# ChipTestBoardQFN32-r2.net
KiCad netlist of a schematic drawn in Altium Designer
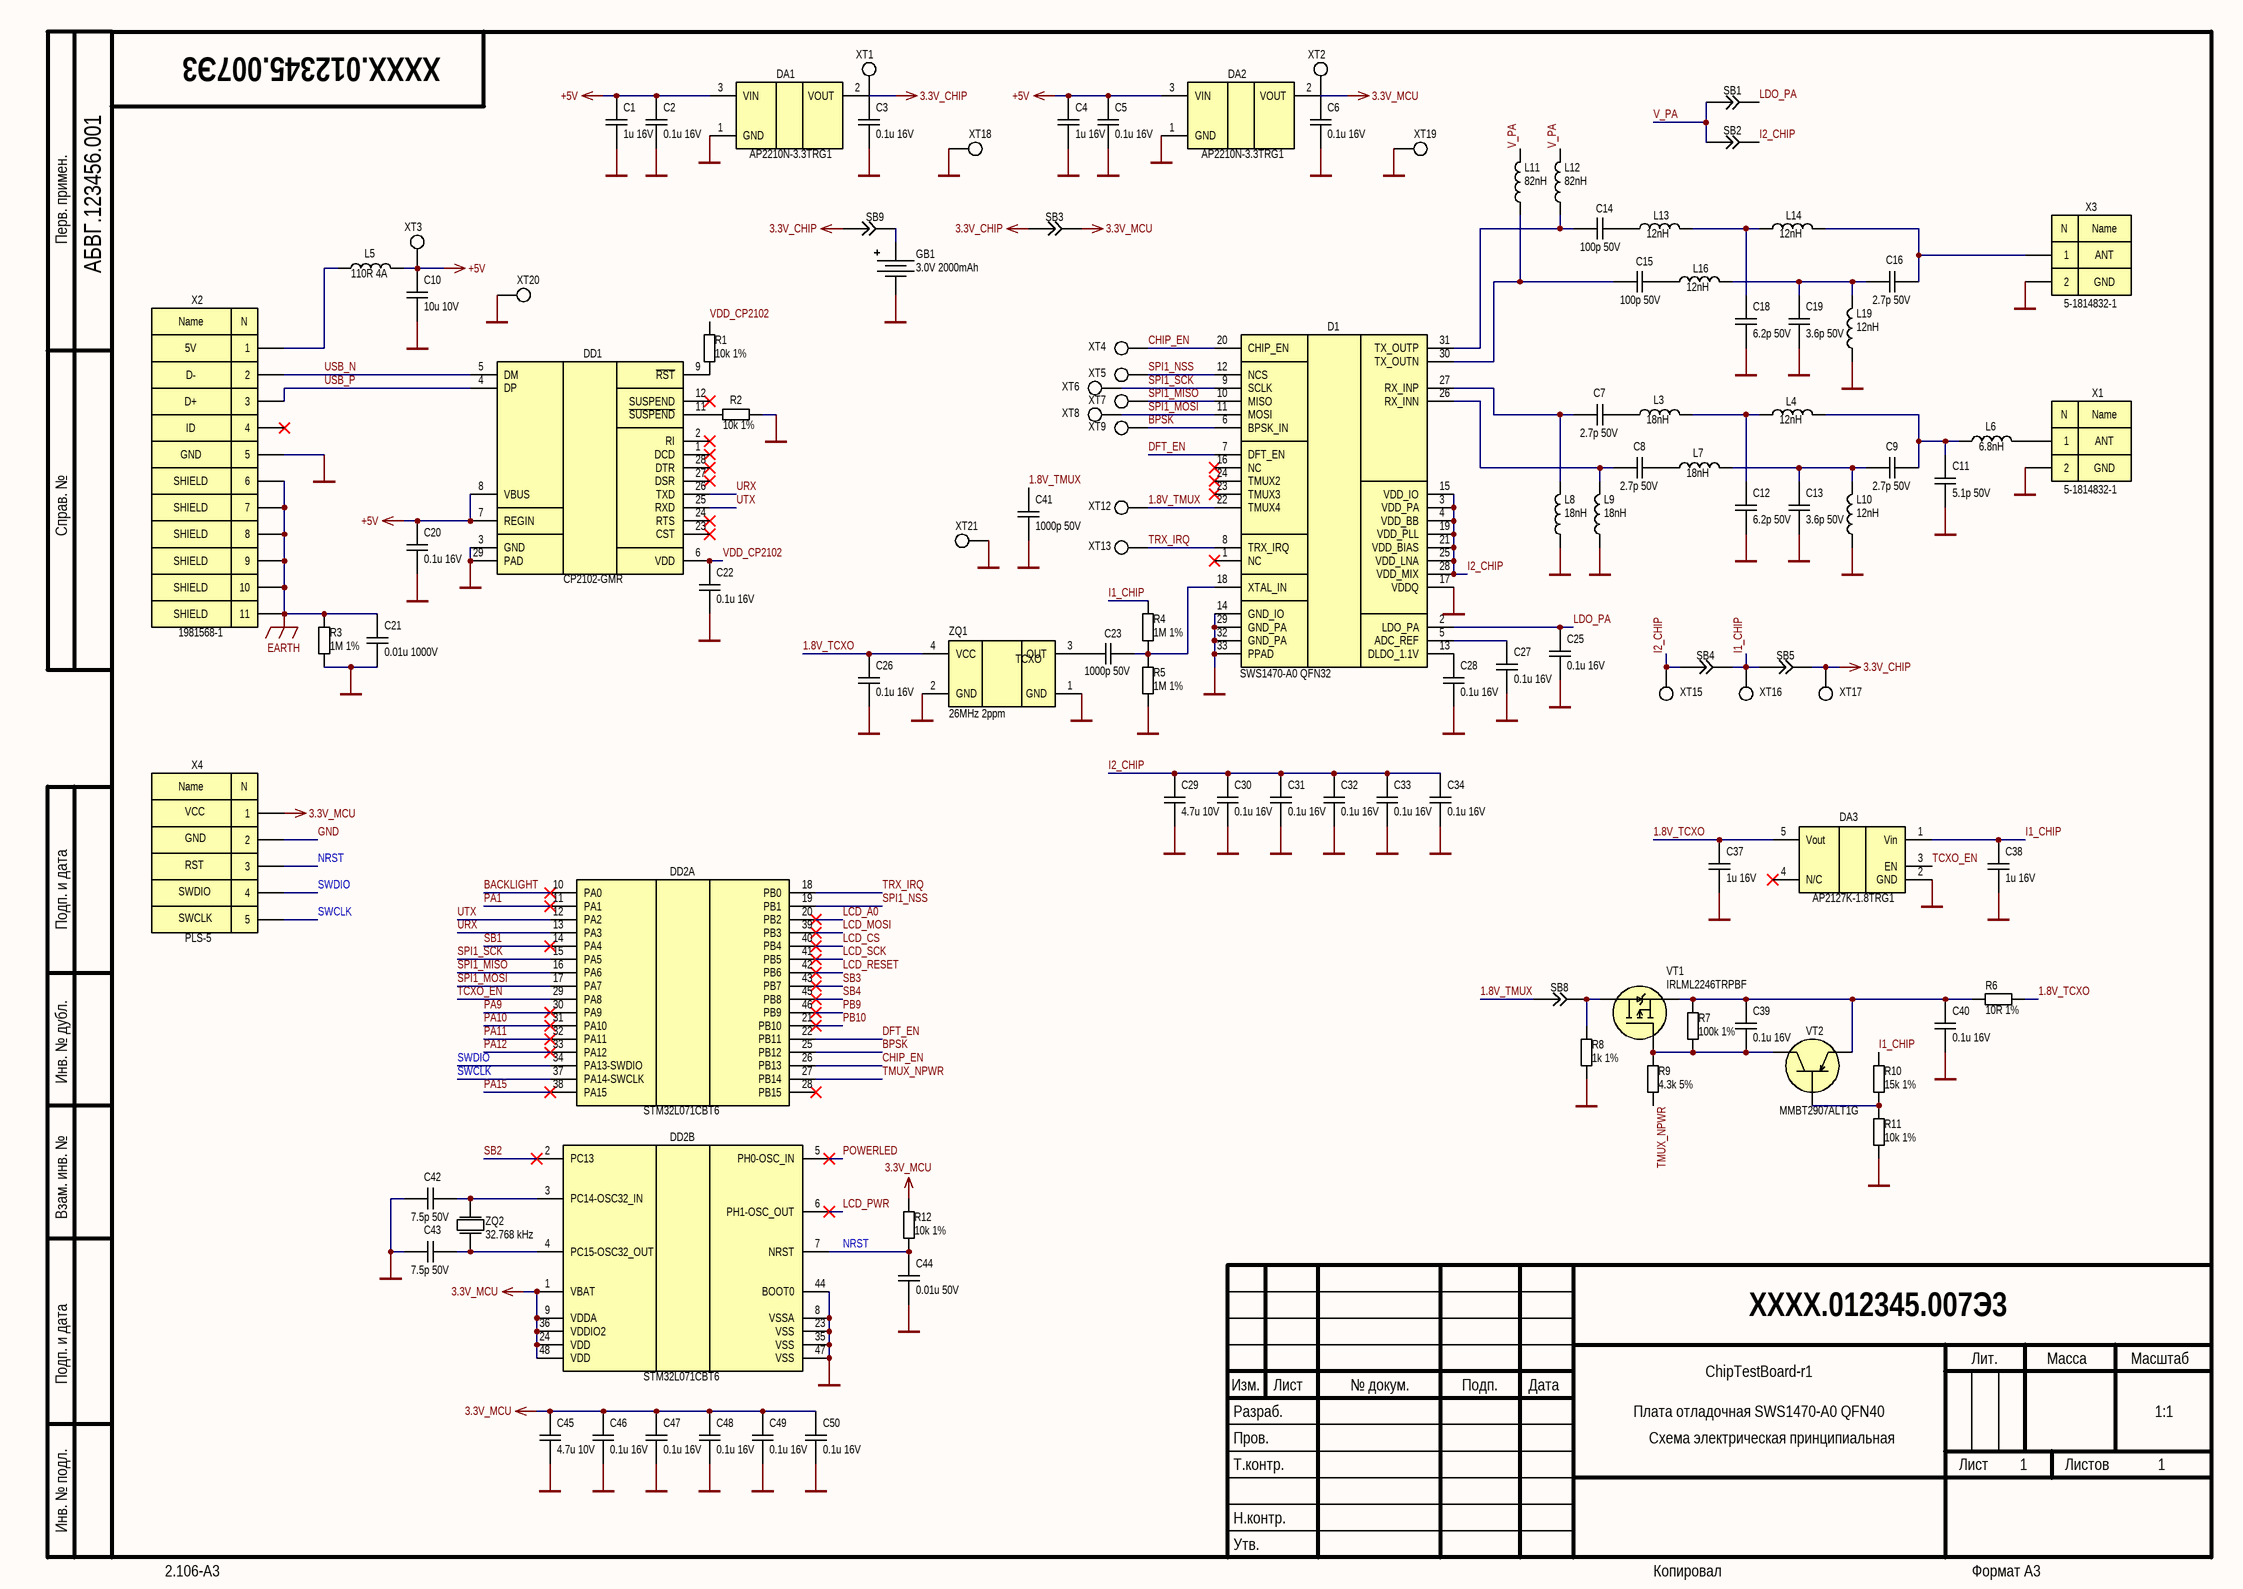
[diagram p0: ChipTestBoardQFN32-r2.SchDoc]

(export (version "E")
  (design (tool "Eeschema 10.0.6"))
  (components
    (comp (ref "C1")
      (value "1u 16V")
      (footprint "C0603")
      (description "CERCAP 1/16V 0603 KX7R")
      (fields (field (name "PARTNUMBER") "CC0603KRX7R7BB105"))
      (libsource (lib "Capacitors") (part "CC0603KRX7R7BB105"))
    )
    (comp (ref "C2")
      (value "0.1u 16V")
      (footprint "C0603")
      (description "CERCAP 0.1/16V 0603 KX7R")
      (fields (field (name "PARTNUMBER") "CC0603KRX7R7BB104"))
      (libsource (lib "Capacitors") (part "CC0603KRX7R7BB104"))
    )
    (comp (ref "C3")
      (value "0.1u 16V")
      (footprint "C0603")
      (description "CERCAP 0.1/16V 0603 KX7R")
      (fields (field (name "PARTNUMBER") "CC0603KRX7R7BB104"))
      (libsource (lib "Capacitors") (part "CC0603KRX7R7BB104"))
    )
    (comp (ref "C4")
      (value "1u 16V")
      (footprint "C0603")
      (description "CERCAP 1/16V 0603 KX7R")
      (fields (field (name "PARTNUMBER") "CC0603KRX7R7BB105"))
      (libsource (lib "Capacitors") (part "CC0603KRX7R7BB105"))
    )
    (comp (ref "C5")
      (value "0.1u 16V")
      (footprint "C0603")
      (description "CERCAP 0.1/16V 0603 KX7R")
      (fields (field (name "PARTNUMBER") "CC0603KRX7R7BB104"))
      (libsource (lib "Capacitors") (part "CC0603KRX7R7BB104"))
    )
    (comp (ref "C6")
      (value "0.1u 16V")
      (footprint "C0603")
      (description "CERCAP 0.1/16V 0603 KX7R")
      (fields (field (name "PARTNUMBER") "CC0603KRX7R7BB104"))
      (libsource (lib "Capacitors") (part "CC0603KRX7R7BB104"))
    )
    (comp (ref "C7")
      (value "2.7p 50V")
      (footprint "C0603")
      (description "CERCAP 2.7p/50V 0603 BNPO")
      (fields (field (name "PARTNUMBER") "CC0603BRNPO9BN2R7"))
      (libsource (lib "Capacitors") (part "CC0603BRNPO9BN2R7"))
    )
    (comp (ref "C8")
      (value "2.7p 50V")
      (footprint "C0603")
      (description "CERCAP 2.7p/50V 0603 BNPO")
      (fields (field (name "PARTNUMBER") "CC0603BRNPO9BN2R7"))
      (libsource (lib "Capacitors") (part "CC0603BRNPO9BN2R7"))
    )
    (comp (ref "C9")
      (value "2.7p 50V")
      (footprint "C0603")
      (description "CERCAP 2.7p/50V 0603 BNPO")
      (fields (field (name "PARTNUMBER") "CC0603BRNPO9BN2R7"))
      (libsource (lib "Capacitors") (part "CC0603BRNPO9BN2R7"))
    )
    (comp (ref "C10")
      (value "10u 10V")
      (footprint "C0805")
      (description "10µF ±10% 10V Ceramic Capacitor X5R 0805 (2012 Metric)")
      (fields (field (name "PARTNUMBER") "CL21A106KPFNNNG"))
      (libsource (lib "Capacitors") (part "CL21A106KPFNNNG"))
    )
    (comp (ref "C11")
      (value "5.1p 50V")
      (footprint "C0603")
      (description "5.1pF ±0.25pF 50V Ceramic Capacitor C0G, NP0 0603 (1608 Metric)")
      (fields (field (name "PARTNUMBER") "CC0603CRNPO9BN5R1"))
      (libsource (lib "Capacitors") (part "CC0603CRNPO9BN5R1"))
    )
    (comp (ref "C12")
      (value "6.2p 50V")
      (footprint "C0603")
      (description "CERCAP 6.2p/50V 0603 BNPO")
      (fields (field (name "PARTNUMBER") "CC0603BRNPO9BN6R2"))
      (libsource (lib "Capacitors") (part "CC0603BRNPO9BN6R2"))
    )
    (comp (ref "C13")
      (value "3.6p 50V")
      (footprint "C0603")
      (description "CERCAP 3.6p/50V 0603 BNPO")
      (fields (field (name "PARTNUMBER") "CC0603BRNPO9BN3R6"))
      (libsource (lib "Capacitors") (part "CC0603BRNPO9BN3R6"))
    )
    (comp (ref "C14")
      (value "100p 50V")
      (footprint "C0603")
      (description "CERCAP 100p/50V 0603 JX7R")
      (fields (field (name "PARTNUMBER") "CC0603JRNPO9BN101"))
      (libsource (lib "Capacitors") (part "CC0603JRNPO9BN101"))
    )
    (comp (ref "C15")
      (value "100p 50V")
      (footprint "C0603")
      (description "CERCAP 100p/50V 0603 JX7R")
      (fields (field (name "PARTNUMBER") "CC0603JRNPO9BN101"))
      (libsource (lib "Capacitors") (part "CC0603JRNPO9BN101"))
    )
    (comp (ref "C16")
      (value "2.7p 50V")
      (footprint "C0603")
      (description "CERCAP 2.7p/50V 0603 BNPO")
      (fields (field (name "PARTNUMBER") "CC0603BRNPO9BN2R7"))
      (libsource (lib "Capacitors") (part "CC0603BRNPO9BN2R7"))
    )
    (comp (ref "C18")
      (value "6.2p 50V")
      (footprint "C0603")
      (description "CERCAP 6.2p/50V 0603 BNPO")
      (fields (field (name "PARTNUMBER") "CC0603BRNPO9BN6R2"))
      (libsource (lib "Capacitors") (part "CC0603BRNPO9BN6R2"))
    )
    (comp (ref "C19")
      (value "3.6p 50V")
      (footprint "C0603")
      (description "CERCAP 3.6p/50V 0603 BNPO")
      (fields (field (name "PARTNUMBER") "CC0603BRNPO9BN3R6"))
      (libsource (lib "Capacitors") (part "CC0603BRNPO9BN3R6"))
    )
    (comp (ref "C20")
      (value "0.1u 16V")
      (footprint "C0603")
      (description "CERCAP 0.1/16V 0603 KX7R")
      (fields (field (name "PARTNUMBER") "CC0603KRX7R7BB104"))
      (libsource (lib "Capacitors") (part "CC0603KRX7R7BB104"))
    )
    (comp (ref "C21")
      (value "0.01u 1000V")
      (footprint "C1206")
      (description "CAP CER 10000PF 1KV X7R 1206")
      (fields (field (name "PARTNUMBER") "CC1206KKX7RCBB103"))
      (libsource (lib "Capacitors") (part "CC1206KKX7RCBB103"))
    )
    (comp (ref "C22")
      (value "0.1u 16V")
      (footprint "C0603")
      (description "CERCAP 0.1/16V 0603 KX7R")
      (fields (field (name "PARTNUMBER") "CC0603KRX7R7BB104"))
      (libsource (lib "Capacitors") (part "CC0603KRX7R7BB104"))
    )
    (comp (ref "C23")
      (value "1000p 50V")
      (footprint "C0603")
      (description "CERCAP 1000p/50V 0603 JNPO")
      (fields (field (name "PARTNUMBER") "CC0603JRNPO9BN102"))
      (libsource (lib "Capacitors") (part "CC0603JRNPO9BN102"))
    )
    (comp (ref "C25")
      (value "0.1u 16V")
      (footprint "C0603")
      (description "CERCAP 0.1/16V 0603 KX7R")
      (fields (field (name "PARTNUMBER") "CC0603KRX7R7BB104"))
      (libsource (lib "Capacitors") (part "CC0603KRX7R7BB104"))
    )
    (comp (ref "C26")
      (value "0.1u 16V")
      (footprint "C0603")
      (description "CERCAP 0.1/16V 0603 KX7R")
      (fields (field (name "PARTNUMBER") "CC0603KRX7R7BB104"))
      (libsource (lib "Capacitors") (part "CC0603KRX7R7BB104"))
    )
    (comp (ref "C27")
      (value "0.1u 16V")
      (footprint "C0603")
      (description "CERCAP 0.1/16V 0603 KX7R")
      (fields (field (name "PARTNUMBER") "CC0603KRX7R7BB104"))
      (libsource (lib "Capacitors") (part "CC0603KRX7R7BB104"))
    )
    (comp (ref "C28")
      (value "0.1u 16V")
      (footprint "C0603")
      (description "CERCAP 0.1/16V 0603 KX7R")
      (fields (field (name "PARTNUMBER") "CC0603KRX7R7BB104"))
      (libsource (lib "Capacitors") (part "CC0603KRX7R7BB104"))
    )
    (comp (ref "C29")
      (value "4.7u 10V")
      (footprint "C0603")
      (description "CERCAP 4.7/10V 0603 KX5R")
      (fields (field (name "PARTNUMBER") "CC0603KRX5R6BB475"))
      (libsource (lib "Capacitors") (part "CC0603KRX5R6BB475"))
    )
    (comp (ref "C30")
      (value "0.1u 16V")
      (footprint "C0603")
      (description "CERCAP 0.1/16V 0603 KX7R")
      (fields (field (name "PARTNUMBER") "CC0603KRX7R7BB104"))
      (libsource (lib "Capacitors") (part "CC0603KRX7R7BB104"))
    )
    (comp (ref "C31")
      (value "0.1u 16V")
      (footprint "C0603")
      (description "CERCAP 0.1/16V 0603 KX7R")
      (fields (field (name "PARTNUMBER") "CC0603KRX7R7BB104"))
      (libsource (lib "Capacitors") (part "CC0603KRX7R7BB104"))
    )
    (comp (ref "C32")
      (value "0.1u 16V")
      (footprint "C0603")
      (description "CERCAP 0.1/16V 0603 KX7R")
      (fields (field (name "PARTNUMBER") "CC0603KRX7R7BB104"))
      (libsource (lib "Capacitors") (part "CC0603KRX7R7BB104"))
    )
    (comp (ref "C33")
      (value "0.1u 16V")
      (footprint "C0603")
      (description "CERCAP 0.1/16V 0603 KX7R")
      (fields (field (name "PARTNUMBER") "CC0603KRX7R7BB104"))
      (libsource (lib "Capacitors") (part "CC0603KRX7R7BB104"))
    )
    (comp (ref "C34")
      (value "0.1u 16V")
      (footprint "C0603")
      (description "CERCAP 0.1/16V 0603 KX7R")
      (fields (field (name "PARTNUMBER") "CC0603KRX7R7BB104"))
      (libsource (lib "Capacitors") (part "CC0603KRX7R7BB104"))
    )
    (comp (ref "C37")
      (value "1u 16V")
      (footprint "C0603")
      (description "CERCAP 1/16V 0603 KX7R")
      (fields (field (name "PARTNUMBER") "CC0603KRX7R7BB105"))
      (libsource (lib "Capacitors") (part "CC0603KRX7R7BB105"))
    )
    (comp (ref "C38")
      (value "1u 16V")
      (footprint "C0603")
      (description "CERCAP 1/16V 0603 KX7R")
      (fields (field (name "PARTNUMBER") "CC0603KRX7R7BB105"))
      (libsource (lib "Capacitors") (part "CC0603KRX7R7BB105"))
    )
    (comp (ref "C39")
      (value "0.1u 16V")
      (footprint "C0603")
      (description "CERCAP 0.1/16V 0603 KX7R")
      (fields (field (name "PARTNUMBER") "CC0603KRX7R7BB104"))
      (libsource (lib "Capacitors") (part "CC0603KRX7R7BB104"))
    )
    (comp (ref "C40")
      (value "0.1u 16V")
      (footprint "C0603")
      (description "CERCAP 0.1/16V 0603 KX7R")
      (fields (field (name "PARTNUMBER") "CC0603KRX7R7BB104"))
      (libsource (lib "Capacitors") (part "CC0603KRX7R7BB104"))
    )
    (comp (ref "C41")
      (value "1000p 50V")
      (footprint "C0603")
      (description "CERCAP 1000p/50V 0603 JNPO")
      (fields (field (name "PARTNUMBER") "CC0603JRNPO9BN102"))
      (libsource (lib "Capacitors") (part "CC0603JRNPO9BN102"))
    )
    (comp (ref "C42")
      (value "7.5p 50V")
      (footprint "C0603")
      (description "CAP CER 7.5PF 50V NPO 0603")
      (fields (field (name "PARTNUMBER") "CC0603CRNPO9BN7R5"))
      (libsource (lib "Capacitors") (part "CC0603CRNPO9BN7R5"))
    )
    (comp (ref "C43")
      (value "7.5p 50V")
      (footprint "C0603")
      (description "CAP CER 7.5PF 50V NPO 0603")
      (fields (field (name "PARTNUMBER") "CC0603CRNPO9BN7R5"))
      (libsource (lib "Capacitors") (part "CC0603CRNPO9BN7R5"))
    )
    (comp (ref "C44")
      (value "0.01u 50V")
      (footprint "C0603")
      (description "CAP CER 10000PF 50V X7R 0603")
      (fields (field (name "PARTNUMBER") "CC0603KRX7R9BB103"))
      (libsource (lib "Capacitors") (part "CC0603KRX7R9BB103"))
    )
    (comp (ref "C45")
      (value "4.7u 10V")
      (footprint "C0603")
      (description "CERCAP 4.7/10V 0603 KX5R")
      (fields (field (name "PARTNUMBER") "CC0603KRX5R6BB475"))
      (libsource (lib "Capacitors") (part "CC0603KRX5R6BB475"))
    )
    (comp (ref "C46")
      (value "0.1u 16V")
      (footprint "C0603")
      (description "CERCAP 0.1/16V 0603 KX7R")
      (fields (field (name "PARTNUMBER") "CC0603KRX7R7BB104"))
      (libsource (lib "Capacitors") (part "CC0603KRX7R7BB104"))
    )
    (comp (ref "C47")
      (value "0.1u 16V")
      (footprint "C0603")
      (description "CERCAP 0.1/16V 0603 KX7R")
      (fields (field (name "PARTNUMBER") "CC0603KRX7R7BB104"))
      (libsource (lib "Capacitors") (part "CC0603KRX7R7BB104"))
    )
    (comp (ref "C48")
      (value "0.1u 16V")
      (footprint "C0603")
      (description "CERCAP 0.1/16V 0603 KX7R")
      (fields (field (name "PARTNUMBER") "CC0603KRX7R7BB104"))
      (libsource (lib "Capacitors") (part "CC0603KRX7R7BB104"))
    )
    (comp (ref "C49")
      (value "0.1u 16V")
      (footprint "C0603")
      (description "CERCAP 0.1/16V 0603 KX7R")
      (fields (field (name "PARTNUMBER") "CC0603KRX7R7BB104"))
      (libsource (lib "Capacitors") (part "CC0603KRX7R7BB104"))
    )
    (comp (ref "C50")
      (value "0.1u 16V")
      (footprint "C0603")
      (description "CERCAP 0.1/16V 0603 KX7R")
      (fields (field (name "PARTNUMBER") "CC0603KRX7R7BB104"))
      (libsource (lib "Capacitors") (part "CC0603KRX7R7BB104"))
    )
    (comp (ref "D1")
      (value "SWS1470-A0 QFN32")
      (footprint "QFN32")
      (description "Waviot NB-Fi RF Transceiver QFN32")
      (libsource (lib "Integrated Circuits (ICs)") (part "SWS1470-A0 QFN32"))
    )
    (comp (ref "DA1")
      (value "AP2210N-3.3TRG1")
      (footprint "SOT23-3L")
      (description "IC REG LINEAR 3.3V 300MA SOT23-3")
      (libsource (lib "Integrated Circuits (ICs)") (part "AP2210N-3.3TRG1"))
    )
    (comp (ref "DA2")
      (value "AP2210N-3.3TRG1")
      (footprint "SOT23-3L")
      (description "IC REG LINEAR 3.3V 300MA SOT23-3")
      (libsource (lib "Integrated Circuits (ICs)") (part "AP2210N-3.3TRG1"))
    )
    (comp (ref "DA3")
      (value "AP2127K-1.8TRG1")
      (footprint "SOT23-5")
      (description "LDO Voltage Regulators 1.8V 80mA CMOS LDO w/Enable")
      (libsource (lib "Integrated Circuits (ICs)") (part "AP2127K-1.8TRG1"))
    )
    (comp (ref "DD1")
      (value "CP2102-GMR")
      (footprint "QFN28")
      (description "IC USB-TO-UART BRIDGE 28VQFN")
      (libsource (lib "Integrated Circuits (ICs)") (part "CP2102-GMR"))
    )
    (comp (ref "DD2")
      (value "STM32L071CBT6")
      (footprint "LQFP48_L")
      (description "ARM Microcontrollers - MCU Ultra-low-power ARM Cortex-M0+ MCU with 64/192-Kbytes Flash, 32 MHz CPU")
      (libsource (lib "Integrated Circuits (ICs)") (part "STM32L071CBT6"))
    )
    (comp (ref "GB1")
      (value "3.0V 2000mAh")
      (footprint "BAT14505-Board")
      (description "Lithium Battery CR14505 3.0V 2000mAh -30..75C")
      (fields (field (name "PARTNUMBER") "CR14505BL-AX"))
      (libsource (lib "Battery Products") (part "CR14505BL-AX"))
    )
    (comp (ref "L3")
      (value "18nH")
      (footprint "L0603_LQW")
      (description "FIXED IND 18NH 550MA 160 MOHM")
      (fields (field (name "PARTNUMBER") "LQW18AN18NG00D"))
      (libsource (lib "Inductors, Coils, Chokes") (part "LQW18AN18NG00D"))
    )
    (comp (ref "L4")
      (value "12nH")
      (footprint "L0603_LQW")
      (description "FIXED IND 12NH 600MA 130 MOHM")
      (fields (field (name "PARTNUMBER") "LQW18AN12NG00D"))
      (libsource (lib "Inductors, Coils, Chokes") (part "LQW18AN12NG00D"))
    )
    (comp (ref "L5")
      (value "110R 4A")
      (footprint "L1806")
      (description "FERRITE BEAD 110 OHM 1806 1LN")
      (fields (field (name "PARTNUMBER") "FBMJ4516HS111-T"))
      (libsource (lib "Filters") (part "FBMJ4516HS111-T"))
    )
    (comp (ref "L6")
      (value "6.8nH")
      (footprint "L0603_LQW")
      (description "FIXED IND 6.8NH 750MA 82 MOHM")
      (fields (field (name "PARTNUMBER") "LQW18AN6N8C00D"))
      (libsource (lib "Inductors, Coils, Chokes") (part "LQW18AN6N8C00D"))
    )
    (comp (ref "L7")
      (value "18nH")
      (footprint "L0603_LQW")
      (description "FIXED IND 18NH 550MA 160 MOHM")
      (fields (field (name "PARTNUMBER") "LQW18AN18NG00D"))
      (libsource (lib "Inductors, Coils, Chokes") (part "LQW18AN18NG00D"))
    )
    (comp (ref "L8")
      (value "18nH")
      (footprint "L0603_LQW")
      (description "FIXED IND 18NH 550MA 160 MOHM")
      (fields (field (name "PARTNUMBER") "LQW18AN18NG00D"))
      (libsource (lib "Inductors, Coils, Chokes") (part "LQW18AN18NG00D"))
    )
    (comp (ref "L9")
      (value "18nH")
      (footprint "L0603_LQW")
      (description "FIXED IND 18NH 550MA 160 MOHM")
      (fields (field (name "PARTNUMBER") "LQW18AN18NG00D"))
      (libsource (lib "Inductors, Coils, Chokes") (part "LQW18AN18NG00D"))
    )
    (comp (ref "L10")
      (value "12nH")
      (footprint "L0603_LQW")
      (description "FIXED IND 12NH 600MA 130 MOHM")
      (fields (field (name "PARTNUMBER") "LQW18AN12NG00D"))
      (libsource (lib "Inductors, Coils, Chokes") (part "LQW18AN12NG00D"))
    )
    (comp (ref "L11")
      (value "82nH")
      (footprint "L0603_LQW")
      (description "FIXED IND 82NH 250MA 600 MOHM")
      (fields (field (name "PARTNUMBER") "LQW18AN82NG00D"))
      (libsource (lib "Inductors, Coils, Chokes") (part "LQW18AN82NG00D"))
    )
    (comp (ref "L12")
      (value "82nH")
      (footprint "L0603_LQW")
      (description "FIXED IND 82NH 250MA 600 MOHM")
      (fields (field (name "PARTNUMBER") "LQW18AN82NG00D"))
      (libsource (lib "Inductors, Coils, Chokes") (part "LQW18AN82NG00D"))
    )
    (comp (ref "L13")
      (value "12nH")
      (footprint "L0603_LQW")
      (description "FIXED IND 12NH 600MA 130 MOHM")
      (fields (field (name "PARTNUMBER") "LQW18AN12NG00D"))
      (libsource (lib "Inductors, Coils, Chokes") (part "LQW18AN12NG00D"))
    )
    (comp (ref "L14")
      (value "12nH")
      (footprint "L0603_LQW")
      (description "FIXED IND 12NH 600MA 130 MOHM")
      (fields (field (name "PARTNUMBER") "LQW18AN12NG00D"))
      (libsource (lib "Inductors, Coils, Chokes") (part "LQW18AN12NG00D"))
    )
    (comp (ref "L16")
      (value "12nH")
      (footprint "L0603_LQW")
      (description "FIXED IND 12NH 600MA 130 MOHM")
      (fields (field (name "PARTNUMBER") "LQW18AN12NG00D"))
      (libsource (lib "Inductors, Coils, Chokes") (part "LQW18AN12NG00D"))
    )
    (comp (ref "L19")
      (value "12nH")
      (footprint "L0603_LQW")
      (description "FIXED IND 12NH 600MA 130 MOHM")
      (fields (field (name "PARTNUMBER") "LQW18AN12NG00D"))
      (libsource (lib "Inductors, Coils, Chokes") (part "LQW18AN12NG00D"))
    )
    (comp (ref "R1")
      (value "10k 1%")
      (footprint "R0603")
      (description "RES 0603 10K 1%")
      (fields (field (name "PARTNUMBER") "RC0603FR-0710KL"))
      (libsource (lib "Resistors") (part "RC0603FR-0710KL"))
    )
    (comp (ref "R2")
      (value "10k 1%")
      (footprint "R0603")
      (description "RES 0603 10K 1%")
      (fields (field (name "PARTNUMBER") "RC0603FR-0710KL"))
      (libsource (lib "") (part "RC0603FR-0710KL_1"))
    )
    (comp (ref "R3")
      (value "1M 1%")
      (footprint "R0603")
      (description "1 MOhms ±1% 0.1W, 1/10W Chip Resistor 0603 (1608 Metric) Moisture Resistant Thick Film")
      (fields (field (name "PARTNUMBER") "RC0603FR-071ML"))
      (libsource (lib "Resistors") (part "RC0603FR-071ML"))
    )
    (comp (ref "R4")
      (value "1M 1%")
      (footprint "R0603")
      (description "1 MOhms ±1% 0.1W, 1/10W Chip Resistor 0603 (1608 Metric) Moisture Resistant Thick Film")
      (fields (field (name "PARTNUMBER") "RC0603FR-071ML"))
      (libsource (lib "Resistors") (part "RC0603FR-071ML"))
    )
    (comp (ref "R5")
      (value "1M 1%")
      (footprint "R0603")
      (description "1 MOhms ±1% 0.1W, 1/10W Chip Resistor 0603 (1608 Metric) Moisture Resistant Thick Film")
      (fields (field (name "PARTNUMBER") "RC0603FR-071ML"))
      (libsource (lib "Resistors") (part "RC0603FR-071ML"))
    )
    (comp (ref "R6")
      (value "10R 1%")
      (footprint "R0603")
      (description "RES SMD 10 OHM 1% 1/10W 0603")
      (fields (field (name "PARTNUMBER") "RC0603FR-0710RL"))
      (libsource (lib "Resistors") (part "RC0603FR-0710RL"))
    )
    (comp (ref "R7")
      (value "100k 1%")
      (footprint "R0603")
      (description "100 kOhms ±1% 0.1W, 1/10W Chip Resistor 0603 (1608 Metric) Moisture Resistant Thick Film")
      (fields (field (name "PARTNUMBER") "RC0603FR-07100KL"))
      (libsource (lib "Resistors") (part "RC0603FR-07100KL"))
    )
    (comp (ref "R8")
      (value "1k 1%")
      (footprint "R0603")
      (description "RES 0603 1K 1%")
      (fields (field (name "PARTNUMBER") "RC0603FR-071KL"))
      (libsource (lib "Resistors") (part "RC0603FR-071KL"))
    )
    (comp (ref "R9")
      (value "4.3k 5%")
      (footprint "R0603")
      (description "RES 0603 4.3K 5%")
      (fields (field (name "PARTNUMBER") "RC0603JR-074K3L"))
      (libsource (lib "Resistors") (part "RC0603JR-074K3L"))
    )
    (comp (ref "R10")
      (value "15k 1%")
      (footprint "R0603")
      (description "RES 0603 15K 1%")
      (fields (field (name "PARTNUMBER") "RC0603FR-0715KL"))
      (libsource (lib "Resistors") (part "RC0603FR-0715KL"))
    )
    (comp (ref "R11")
      (value "10k 1%")
      (footprint "R0603")
      (description "RES 0603 10K 1%")
      (fields (field (name "PARTNUMBER") "RC0603FR-0710KL"))
      (libsource (lib "Resistors") (part "RC0603FR-0710KL"))
    )
    (comp (ref "R12")
      (value "10k 1%")
      (footprint "R0603")
      (description "RES 0603 10K 1%")
      (fields (field (name "PARTNUMBER") "RC0603FR-0710KL"))
      (libsource (lib "Resistors") (part "RC0603FR-0710KL"))
    )
    (comp (ref "SB1")
      (value "Jumper Solder")
      (footprint "SB0805")
      (description "Jumper Solder 0805")
      (libsource (lib "Connectors") (part "JS_0805"))
    )
    (comp (ref "SB2")
      (value "Jumper Solder")
      (footprint "SB0805")
      (description "Jumper Solder 0805")
      (libsource (lib "Connectors") (part "JS_0805"))
    )
    (comp (ref "SB3")
      (value "Jumper Solder")
      (footprint "SB0805")
      (description "Jumper Solder 0805")
      (libsource (lib "Connectors") (part "JS_0805"))
    )
    (comp (ref "SB4")
      (value "Jumper Solder")
      (footprint "SB0805")
      (description "Jumper Solder 0805")
      (libsource (lib "Connectors") (part "JS_0805"))
    )
    (comp (ref "SB5")
      (value "Jumper Solder")
      (footprint "SB0805")
      (description "Jumper Solder 0805")
      (libsource (lib "Connectors") (part "JS_0805"))
    )
    (comp (ref "SB8")
      (value "Jumper Solder")
      (footprint "SB0805")
      (description "Jumper Solder 0805")
      (libsource (lib "Connectors") (part "JS_0805"))
    )
    (comp (ref "SB9")
      (value "Jumper Solder")
      (footprint "SB0805")
      (description "Jumper Solder 0805")
      (libsource (lib "Connectors") (part "JS_0805"))
    )
    (comp (ref "VT1")
      (value "IRLML2246TRPBF")
      (footprint "SOT23-3L")
      (description "MOSFET MOSFT PCh -20V -2.6A 135mOhm -2.5V cpbl")
      (libsource (lib "Discrete Semiconductor Products") (part "IRLML2246TRPBF"))
    )
    (comp (ref "VT2")
      (value "MMBT2907ALT1G")
      (footprint "SOT23-3L")
      (description "TRANS PNP 60V 0.6A SOT23")
      (libsource (lib "Discrete Semiconductor Products") (part "MMBT2907ALT1G"))
    )
    (comp (ref "X1")
      (value "5-1814832-1")
      (footprint "5-1814832-1")
      (description "CONN SMA JACK STR 50 OHM PCB")
      (libsource (lib "Connectors") (part "5-1814832-1"))
    )
    (comp (ref "X2")
      (value "1981568-1")
      (footprint "1981568-1")
      (description "CONN RCPT USB2.0 MICRO B SMD R/A")
      (libsource (lib "Connectors") (part "1981568-1"))
    )
    (comp (ref "X3")
      (value "5-1814832-1")
      (footprint "5-1814832-1")
      (description "CONN SMA JACK STR 50 OHM PCB")
      (libsource (lib "Connectors") (part "5-1814832-1"))
    )
    (comp (ref "X4")
      (value "PLS-5")
      (footprint "PLS-5-2.54-PCB")
      (description "PLS-5-2.54")
      (libsource (lib "Connectors") (part "PLS-5"))
    )
    (comp (ref "XT1")
      (value "3.3V_MCU")
      (footprint "PAD-d1.0-x1.6-y1.6")
      (libsource (lib "Special") (part "PIN"))
    )
    (comp (ref "XT2")
      (value "3.3V_CHIP")
      (footprint "PAD-d1.0-x1.6-y1.6")
      (libsource (lib "Special") (part "PIN"))
    )
    (comp (ref "XT3")
      (value "+5V_EXT")
      (footprint "PAD-d1.0-x1.6-y1.6")
      (libsource (lib "Special") (part "PIN"))
    )
    (comp (ref "XT4")
      (value "CHIP_EN")
      (footprint "PAD-d1.0-x1.6-y1.6")
      (libsource (lib "Special") (part "PIN"))
    )
    (comp (ref "XT5") (value "NSS") (footprint "PAD-d1.0-x1.6-y1.6") (libsource (lib "Special") (part "PIN")))
    (comp (ref "XT6") (value "SCK") (footprint "PAD-d1.0-x1.6-y1.6") (libsource (lib "Special") (part "PIN")))
    (comp (ref "XT7")
      (value "MISO")
      (footprint "PAD-d1.0-x1.6-y1.6")
      (libsource (lib "Special") (part "PIN"))
    )
    (comp (ref "XT8")
      (value "MOSI")
      (footprint "PAD-d1.0-x1.6-y1.6")
      (libsource (lib "Special") (part "PIN"))
    )
    (comp (ref "XT9")
      (value "BPSK_IN")
      (footprint "PAD-d1.0-x1.6-y1.6")
      (libsource (lib "Special") (part "PIN"))
    )
    (comp (ref "XT12")
      (value "1.8V_TMUX")
      (footprint "PAD-d1.0-x1.6-y1.6")
      (libsource (lib "Special") (part "PIN"))
    )
    (comp (ref "XT13")
      (value "TRX_IR")
      (footprint "PAD-d1.0-x1.6-y1.6")
      (libsource (lib "Special") (part "PIN"))
    )
    (comp (ref "XT15")
      (value "I2_CHIP")
      (footprint "PAD-d1.0-x1.6-y1.6")
      (libsource (lib "Special") (part "PIN"))
    )
    (comp (ref "XT16")
      (value "I1_CHIP")
      (footprint "PAD-d1.0-x1.6-y1.6")
      (libsource (lib "Special") (part "PIN"))
    )
    (comp (ref "XT17")
      (value "3.3V_CHIP")
      (footprint "PAD-d1.0-x1.6-y1.6")
      (libsource (lib "Special") (part "PIN"))
    )
    (comp (ref "XT18")
      (value "GND")
      (footprint "PAD-d1.0-x1.6-y1.6")
      (libsource (lib "Special") (part "PIN"))
    )
    (comp (ref "XT19")
      (value "GND")
      (footprint "PAD-d1.0-x1.6-y1.6")
      (libsource (lib "Special") (part "PIN"))
    )
    (comp (ref "XT20")
      (value "GND")
      (footprint "PAD-d1.0-x1.6-y1.6")
      (libsource (lib "Special") (part "PIN"))
    )
    (comp (ref "XT21")
      (value "GND")
      (footprint "PAD-d1.0-x1.6-y1.6")
      (libsource (lib "Special") (part "PIN"))
    )
    (comp (ref "ZQ1")
      (value "26MHz 2ppm")
      (footprint "QSMD2.0x1.6x0.7")
      (description "TCXO Oscillator 4-pin")
      (fields (field (name "PARTNUMBER") "NT2016SA-26.000000MHZ-NBG2"))
      (libsource (lib "Crystals, Oscillators, Resonators") (part "NT2016SA-26.000000MHZ-NBG2"))
    )
    (comp (ref "ZQ2")
      (value "32.768 kHz")
      (footprint "QSMD3.2X1.5X0.8")
      (description "Crystals 32.768KHz 12.5pF -40C +85C")
      (fields (field (name "PARTNUMBER") "KX-327NHT 32.768 kHz"))
      (libsource (lib "Crystals, Oscillators, Resonators") (part "KX-327NHT 32.768 kHz"))
    )
  )
  (nets
    (net (code "1") (name "+5V") (class "Default")
      (node (ref "C1") (pin "2") (pinfunction "2_2") (pintype "passive"))
      (node (ref "C10") (pin "2") (pinfunction "2_2") (pintype "passive"))
      (node (ref "C2") (pin "2") (pinfunction "2_2") (pintype "passive"))
      (node (ref "C20") (pin "2") (pinfunction "2_2") (pintype "passive"))
      (node (ref "C4") (pin "2") (pinfunction "2_2") (pintype "passive"))
      (node (ref "C5") (pin "2") (pinfunction "2_2") (pintype "passive"))
      (node (ref "DA1") (pin "3") (pinfunction "VIN_3") (pintype "passive"))
      (node (ref "DA2") (pin "3") (pinfunction "VIN_3") (pintype "passive"))
      (node (ref "DD1") (pin "7") (pinfunction "REGIN_7") (pintype "passive"))
      (node (ref "DD1") (pin "8") (pinfunction "VBUS_8") (pintype "passive"))
      (node (ref "L5") (pin "2") (pinfunction "2_2") (pintype "passive"))
      (node (ref "XT3") (pin "1") (pinfunction "1_1") (pintype "passive"))
    )
    (net (code "2") (name "/1.8V_TCXO") (class "Default")
      (node (ref "C26") (pin "2") (pinfunction "2_2") (pintype "passive"))
      (node (ref "C37") (pin "2") (pinfunction "2_2") (pintype "passive"))
      (node (ref "DA3") (pin "5") (pinfunction "Vout_5") (pintype "passive"))
      (node (ref "R6") (pin "2") (pinfunction "2_2") (pintype "passive"))
      (node (ref "ZQ1") (pin "4") (pinfunction "VCC_4") (pintype "passive"))
    )
    (net (code "3") (name "/1.8V_TMUX") (class "Default")
      (node (ref "C41") (pin "1") (pinfunction "1_1") (pintype "passive"))
      (node (ref "D1") (pin "22") (pinfunction "TMUX4_22") (pintype "passive"))
      (node (ref "SB8") (pin "1") (pinfunction "1_1") (pintype "passive"))
      (node (ref "XT12") (pin "1") (pinfunction "1_1") (pintype "passive"))
    )
    (net (code "4") (name "/BACKLIGHT") (class "Default")
      (node (ref "DD2") (pin "10") (pinfunction "PA0_10") (pintype "passive+no_connect"))
    )
    (net (code "5") (name "/BPSK") (class "Default")
      (node (ref "D1") (pin "6") (pinfunction "BPSK_IN_6") (pintype "passive"))
      (node (ref "DD2") (pin "25") (pinfunction "PB12_25") (pintype "passive"))
      (node (ref "XT9") (pin "1") (pinfunction "1_1") (pintype "passive"))
    )
    (net (code "6") (name "/CHIP_EN") (class "Default")
      (node (ref "D1") (pin "20") (pinfunction "CHIP_EN_20") (pintype "passive"))
      (node (ref "DD2") (pin "26") (pinfunction "PB13_26") (pintype "passive"))
      (node (ref "XT4") (pin "1") (pinfunction "1_1") (pintype "passive"))
    )
    (net (code "7") (name "/DFT_EN") (class "Default")
      (node (ref "D1") (pin "7") (pinfunction "DFT_EN_7") (pintype "passive"))
      (node (ref "DD2") (pin "22") (pinfunction "PB11_22") (pintype "passive"))
    )
    (net (code "8") (name "/I1_CHIP") (class "Default")
      (node (ref "C38") (pin "2") (pinfunction "2_2") (pintype "passive"))
      (node (ref "DA3") (pin "1") (pinfunction "Vin_1") (pintype "passive"))
      (node (ref "R10") (pin "2") (pinfunction "2_2") (pintype "passive"))
      (node (ref "R4") (pin "2") (pinfunction "2_2") (pintype "passive"))
      (node (ref "SB4") (pin "2") (pinfunction "2_2") (pintype "passive"))
      (node (ref "SB5") (pin "1") (pinfunction "1_1") (pintype "passive"))
      (node (ref "XT16") (pin "1") (pinfunction "1_1") (pintype "passive"))
    )
    (net (code "9") (name "/I2_CHIP") (class "Default")
      (node (ref "C29") (pin "2") (pinfunction "2_2") (pintype "passive"))
      (node (ref "C30") (pin "2") (pinfunction "2_2") (pintype "passive"))
      (node (ref "C31") (pin "2") (pinfunction "2_2") (pintype "passive"))
      (node (ref "C32") (pin "2") (pinfunction "2_2") (pintype "passive"))
      (node (ref "C33") (pin "2") (pinfunction "2_2") (pintype "passive"))
      (node (ref "C34") (pin "2") (pinfunction "2_2") (pintype "passive"))
      (node (ref "D1") (pin "15") (pinfunction "VDD_IO_15") (pintype "passive"))
      (node (ref "D1") (pin "19") (pinfunction "VDD_PLL_19") (pintype "passive"))
      (node (ref "D1") (pin "21") (pinfunction "VDD_BIAS_21") (pintype "passive"))
      (node (ref "D1") (pin "25") (pinfunction "VDD_LNA_25") (pintype "passive"))
      (node (ref "D1") (pin "28") (pinfunction "VDD_MIX_28") (pintype "passive"))
      (node (ref "D1") (pin "3") (pinfunction "VDD_PA_3") (pintype "passive"))
      (node (ref "D1") (pin "4") (pinfunction "VDD_BB_4") (pintype "passive"))
      (node (ref "SB2") (pin "2") (pinfunction "2_2") (pintype "passive"))
      (node (ref "SB4") (pin "1") (pinfunction "1_1") (pintype "passive"))
      (node (ref "XT15") (pin "1") (pinfunction "1_1") (pintype "passive"))
    )
    (net (code "10") (name "/LCD_A0") (class "Default")
      (node (ref "DD2") (pin "20") (pinfunction "PB2_20") (pintype "passive+no_connect"))
    )
    (net (code "11") (name "/LCD_CS") (class "Default")
      (node (ref "DD2") (pin "40") (pinfunction "PB4_40") (pintype "passive+no_connect"))
    )
    (net (code "12") (name "/LCD_MOSI") (class "Default")
      (node (ref "DD2") (pin "39") (pinfunction "PB3_39") (pintype "passive+no_connect"))
    )
    (net (code "13") (name "/LCD_PWR") (class "Default")
      (node (ref "DD2") (pin "6") (pinfunction "PH1-OSC_OUT_6") (pintype "passive+no_connect"))
    )
    (net (code "14") (name "/LCD_RESET") (class "Default")
      (node (ref "DD2") (pin "42") (pinfunction "PB6_42") (pintype "passive+no_connect"))
    )
    (net (code "15") (name "/LCD_SCK") (class "Default")
      (node (ref "DD2") (pin "41") (pinfunction "PB5_41") (pintype "passive+no_connect"))
    )
    (net (code "16") (name "/LDO_PA") (class "Default")
      (node (ref "C25") (pin "2") (pinfunction "2_2") (pintype "passive"))
      (node (ref "D1") (pin "2") (pinfunction "LDO_PA_2") (pintype "passive"))
      (node (ref "SB1") (pin "2") (pinfunction "2_2") (pintype "passive"))
    )
    (net (code "17") (name "/NRST") (class "Default")
      (node (ref "C44") (pin "2") (pinfunction "2_2") (pintype "passive"))
      (node (ref "DD2") (pin "7") (pinfunction "NRST_7") (pintype "passive"))
      (node (ref "R12") (pin "1") (pinfunction "1_1") (pintype "passive"))
      (node (ref "X4") (pin "3") (pinfunction "3_3") (pintype "passive"))
    )
    (net (code "18") (name "/PA1") (class "Default")
      (node (ref "DD2") (pin "11") (pinfunction "PA1_11") (pintype "passive+no_connect"))
    )
    (net (code "19") (name "/PA9") (class "Default")
      (node (ref "DD2") (pin "30") (pinfunction "PA9_30") (pintype "passive+no_connect"))
    )
    (net (code "20") (name "/PA10") (class "Default")
      (node (ref "DD2") (pin "31") (pinfunction "PA10_31") (pintype "passive+no_connect"))
    )
    (net (code "21") (name "/PA11") (class "Default")
      (node (ref "DD2") (pin "32") (pinfunction "PA11_32") (pintype "passive+no_connect"))
    )
    (net (code "22") (name "/PA12") (class "Default")
      (node (ref "DD2") (pin "33") (pinfunction "PA12_33") (pintype "passive+no_connect"))
    )
    (net (code "23") (name "/PA15") (class "Default")
      (node (ref "DD2") (pin "38") (pinfunction "PA15_38") (pintype "passive+no_connect"))
    )
    (net (code "24") (name "/PB9") (class "Default")
      (node (ref "DD2") (pin "46") (pinfunction "PB9_46") (pintype "passive+no_connect"))
    )
    (net (code "25") (name "/PB10") (class "Default")
      (node (ref "DD2") (pin "21") (pinfunction "PB10_21") (pintype "passive+no_connect"))
    )
    (net (code "26") (name "/POWERLED") (class "Default")
      (node (ref "DD2") (pin "5") (pinfunction "PH0-OSC_IN_5") (pintype "passive+no_connect"))
    )
    (net (code "27") (name "/SB1") (class "Default")
      (node (ref "DD2") (pin "14") (pinfunction "PA4_14") (pintype "passive+no_connect"))
    )
    (net (code "28") (name "/SB2") (class "Default")
      (node (ref "DD2") (pin "2") (pinfunction "PC13_2") (pintype "passive+no_connect"))
    )
    (net (code "29") (name "/SB3") (class "Default")
      (node (ref "DD2") (pin "43") (pinfunction "PB7_43") (pintype "passive+no_connect"))
    )
    (net (code "30") (name "/SB4") (class "Default")
      (node (ref "DD2") (pin "45") (pinfunction "PB8_45") (pintype "passive+no_connect"))
    )
    (net (code "31") (name "/SPI1_MISO") (class "Default")
      (node (ref "D1") (pin "10") (pinfunction "MISO_10") (pintype "passive"))
      (node (ref "DD2") (pin "16") (pinfunction "PA6_16") (pintype "passive"))
      (node (ref "XT7") (pin "1") (pinfunction "1_1") (pintype "passive"))
    )
    (net (code "32") (name "/SPI1_MOSI") (class "Default")
      (node (ref "D1") (pin "11") (pinfunction "MOSI_11") (pintype "passive"))
      (node (ref "DD2") (pin "17") (pinfunction "PA7_17") (pintype "passive"))
      (node (ref "XT8") (pin "1") (pinfunction "1_1") (pintype "passive"))
    )
    (net (code "33") (name "/SPI1_NSS") (class "Default")
      (node (ref "D1") (pin "12") (pinfunction "NCS_12") (pintype "passive"))
      (node (ref "DD2") (pin "19") (pinfunction "PB1_19") (pintype "passive"))
      (node (ref "XT5") (pin "1") (pinfunction "1_1") (pintype "passive"))
    )
    (net (code "34") (name "/SPI1_SCK") (class "Default")
      (node (ref "D1") (pin "9") (pinfunction "SCLK_9") (pintype "passive"))
      (node (ref "DD2") (pin "15") (pinfunction "PA5_15") (pintype "passive"))
      (node (ref "XT6") (pin "1") (pinfunction "1_1") (pintype "passive"))
    )
    (net (code "35") (name "/SWCLK") (class "Default")
      (node (ref "DD2") (pin "37") (pinfunction "PA14-SWCLK_37") (pintype "passive"))
      (node (ref "X4") (pin "5") (pinfunction "5_5") (pintype "passive"))
    )
    (net (code "36") (name "/SWDIO") (class "Default")
      (node (ref "DD2") (pin "34") (pinfunction "PA13-SWDIO_34") (pintype "passive"))
      (node (ref "X4") (pin "4") (pinfunction "4_4") (pintype "passive"))
    )
    (net (code "37") (name "/TCXO_EN") (class "Default")
      (node (ref "DA3") (pin "3") (pinfunction "EN_3") (pintype "passive"))
      (node (ref "DD2") (pin "29") (pinfunction "PA8_29") (pintype "passive"))
    )
    (net (code "38") (name "/TMUX_NPWR") (class "Default")
      (node (ref "DD2") (pin "27") (pinfunction "PB14_27") (pintype "passive"))
      (node (ref "R9") (pin "1") (pinfunction "1_1") (pintype "passive"))
    )
    (net (code "39") (name "/TRX_IRQ") (class "Default")
      (node (ref "D1") (pin "8") (pinfunction "TRX_IRQ_8") (pintype "passive"))
      (node (ref "DD2") (pin "18") (pinfunction "PB0_18") (pintype "passive"))
      (node (ref "XT13") (pin "1") (pinfunction "1_1") (pintype "passive"))
    )
    (net (code "40") (name "/URX") (class "Default")
      (node (ref "DD1") (pin "26") (pinfunction "TXD_26") (pintype "passive"))
      (node (ref "DD2") (pin "13") (pinfunction "PA3_13") (pintype "passive"))
    )
    (net (code "41") (name "/USB_N") (class "Default")
      (node (ref "DD1") (pin "5") (pinfunction "DM_5") (pintype "passive"))
      (node (ref "X2") (pin "2") (pinfunction "2_2") (pintype "passive"))
    )
    (net (code "42") (name "/USB_P") (class "Default")
      (node (ref "DD1") (pin "4") (pinfunction "DP_4") (pintype "passive"))
      (node (ref "X2") (pin "3") (pinfunction "3_3") (pintype "passive"))
    )
    (net (code "43") (name "/UTX") (class "Default")
      (node (ref "DD1") (pin "25") (pinfunction "RXD_25") (pintype "passive"))
      (node (ref "DD2") (pin "12") (pinfunction "PA2_12") (pintype "passive"))
    )
    (net (code "44") (name "/VDD_CP2102") (class "Default")
      (node (ref "C22") (pin "2") (pinfunction "2_2") (pintype "passive"))
      (node (ref "DD1") (pin "6") (pinfunction "VDD_6") (pintype "passive"))
      (node (ref "R1") (pin "2") (pinfunction "2_2") (pintype "passive"))
    )
    (net (code "45") (name "/V_PA") (class "Default")
      (node (ref "L11") (pin "2") (pinfunction "2_2") (pintype "passive"))
      (node (ref "L12") (pin "2") (pinfunction "2_2") (pintype "passive"))
      (node (ref "SB1") (pin "1") (pinfunction "1_1") (pintype "passive"))
      (node (ref "SB2") (pin "1") (pinfunction "1_1") (pintype "passive"))
    )
    (net (code "46") (name "3.3V_CHIP") (class "Default")
      (node (ref "C3") (pin "2") (pinfunction "2_2") (pintype "passive"))
      (node (ref "DA1") (pin "2") (pinfunction "VOUT_2") (pintype "passive"))
      (node (ref "SB3") (pin "1") (pinfunction "1_1") (pintype "passive"))
      (node (ref "SB5") (pin "2") (pinfunction "2_2") (pintype "passive"))
      (node (ref "SB9") (pin "1") (pinfunction "1_1") (pintype "passive"))
      (node (ref "XT1") (pin "1") (pinfunction "1_1") (pintype "passive"))
      (node (ref "XT17") (pin "1") (pinfunction "1_1") (pintype "passive"))
    )
    (net (code "47") (name "3.3V_MCU") (class "Default")
      (node (ref "C45") (pin "2") (pinfunction "2_2") (pintype "passive"))
      (node (ref "C46") (pin "2") (pinfunction "2_2") (pintype "passive"))
      (node (ref "C47") (pin "2") (pinfunction "2_2") (pintype "passive"))
      (node (ref "C48") (pin "2") (pinfunction "2_2") (pintype "passive"))
      (node (ref "C49") (pin "2") (pinfunction "2_2") (pintype "passive"))
      (node (ref "C50") (pin "2") (pinfunction "2_2") (pintype "passive"))
      (node (ref "C6") (pin "2") (pinfunction "2_2") (pintype "passive"))
      (node (ref "DA2") (pin "2") (pinfunction "VOUT_2") (pintype "passive"))
      (node (ref "DD2") (pin "1") (pinfunction "VBAT_1") (pintype "passive"))
      (node (ref "DD2") (pin "24") (pinfunction "VDD_24") (pintype "passive"))
      (node (ref "DD2") (pin "36") (pinfunction "VDDIO2_36") (pintype "passive"))
      (node (ref "DD2") (pin "48") (pinfunction "VDD_48") (pintype "passive"))
      (node (ref "DD2") (pin "9") (pinfunction "VDDA_9") (pintype "passive"))
      (node (ref "R12") (pin "2") (pinfunction "2_2") (pintype "passive"))
      (node (ref "SB3") (pin "2") (pinfunction "2_2") (pintype "passive"))
      (node (ref "X4") (pin "1") (pinfunction "1_1") (pintype "passive"))
      (node (ref "XT2") (pin "1") (pinfunction "1_1") (pintype "passive"))
    )
    (net (code "48") (name "EARTH") (class "Default")
      (node (ref "C21") (pin "1") (pinfunction "1_1") (pintype "passive"))
      (node (ref "R3") (pin "2") (pinfunction "2_2") (pintype "passive"))
      (node (ref "X2") (pin "10") (pinfunction "10_10") (pintype "passive"))
      (node (ref "X2") (pin "11") (pinfunction "11_11") (pintype "passive"))
      (node (ref "X2") (pin "6") (pinfunction "6_6") (pintype "passive"))
      (node (ref "X2") (pin "7") (pinfunction "7_7") (pintype "passive"))
      (node (ref "X2") (pin "8") (pinfunction "8_8") (pintype "passive"))
      (node (ref "X2") (pin "9") (pinfunction "9_9") (pintype "passive"))
    )
    (net (code "49") (name "GND") (class "Default")
      (node (ref "C1") (pin "1") (pinfunction "1_1") (pintype "passive"))
      (node (ref "C10") (pin "1") (pinfunction "1_1") (pintype "passive"))
      (node (ref "C11") (pin "1") (pinfunction "1_1") (pintype "passive"))
      (node (ref "C12") (pin "2") (pinfunction "2_2") (pintype "passive"))
      (node (ref "C13") (pin "2") (pinfunction "2_2") (pintype "passive"))
      (node (ref "C18") (pin "2") (pinfunction "2_2") (pintype "passive"))
      (node (ref "C19") (pin "2") (pinfunction "2_2") (pintype "passive"))
      (node (ref "C2") (pin "1") (pinfunction "1_1") (pintype "passive"))
      (node (ref "C20") (pin "1") (pinfunction "1_1") (pintype "passive"))
      (node (ref "C21") (pin "2") (pinfunction "2_2") (pintype "passive"))
      (node (ref "C22") (pin "1") (pinfunction "1_1") (pintype "passive"))
      (node (ref "C25") (pin "1") (pinfunction "1_1") (pintype "passive"))
      (node (ref "C26") (pin "1") (pinfunction "1_1") (pintype "passive"))
      (node (ref "C27") (pin "1") (pinfunction "1_1") (pintype "passive"))
      (node (ref "C28") (pin "1") (pinfunction "1_1") (pintype "passive"))
      (node (ref "C29") (pin "1") (pinfunction "1_1") (pintype "passive"))
      (node (ref "C3") (pin "1") (pinfunction "1_1") (pintype "passive"))
      (node (ref "C30") (pin "1") (pinfunction "1_1") (pintype "passive"))
      (node (ref "C31") (pin "1") (pinfunction "1_1") (pintype "passive"))
      (node (ref "C32") (pin "1") (pinfunction "1_1") (pintype "passive"))
      (node (ref "C33") (pin "1") (pinfunction "1_1") (pintype "passive"))
      (node (ref "C34") (pin "1") (pinfunction "1_1") (pintype "passive"))
      (node (ref "C37") (pin "1") (pinfunction "1_1") (pintype "passive"))
      (node (ref "C38") (pin "1") (pinfunction "1_1") (pintype "passive"))
      (node (ref "C4") (pin "1") (pinfunction "1_1") (pintype "passive"))
      (node (ref "C40") (pin "1") (pinfunction "1_1") (pintype "passive"))
      (node (ref "C41") (pin "2") (pinfunction "2_2") (pintype "passive"))
      (node (ref "C42") (pin "1") (pinfunction "1_1") (pintype "passive"))
      (node (ref "C43") (pin "1") (pinfunction "1_1") (pintype "passive"))
      (node (ref "C44") (pin "1") (pinfunction "1_1") (pintype "passive"))
      (node (ref "C45") (pin "1") (pinfunction "1_1") (pintype "passive"))
      (node (ref "C46") (pin "1") (pinfunction "1_1") (pintype "passive"))
      (node (ref "C47") (pin "1") (pinfunction "1_1") (pintype "passive"))
      (node (ref "C48") (pin "1") (pinfunction "1_1") (pintype "passive"))
      (node (ref "C49") (pin "1") (pinfunction "1_1") (pintype "passive"))
      (node (ref "C5") (pin "1") (pinfunction "1_1") (pintype "passive"))
      (node (ref "C50") (pin "1") (pinfunction "1_1") (pintype "passive"))
      (node (ref "C6") (pin "1") (pinfunction "1_1") (pintype "passive"))
      (node (ref "D1") (pin "14") (pinfunction "GND_IO_14") (pintype "passive"))
      (node (ref "D1") (pin "17") (pinfunction "VDDQ_17") (pintype "passive"))
      (node (ref "D1") (pin "29") (pinfunction "GND_PA_29") (pintype "passive"))
      (node (ref "D1") (pin "32") (pinfunction "GND_PA_32") (pintype "passive"))
      (node (ref "D1") (pin "33") (pinfunction "PPAD_33") (pintype "passive"))
      (node (ref "DA1") (pin "1") (pinfunction "GND_1") (pintype "passive"))
      (node (ref "DA2") (pin "1") (pinfunction "GND_1") (pintype "passive"))
      (node (ref "DA3") (pin "2") (pinfunction "GND_2") (pintype "passive"))
      (node (ref "DD1") (pin "29") (pinfunction "PAD_29") (pintype "passive"))
      (node (ref "DD1") (pin "3") (pinfunction "GND_3") (pintype "passive"))
      (node (ref "DD2") (pin "23") (pinfunction "VSS_23") (pintype "passive"))
      (node (ref "DD2") (pin "35") (pinfunction "VSS_35") (pintype "passive"))
      (node (ref "DD2") (pin "44") (pinfunction "BOOT0_44") (pintype "passive"))
      (node (ref "DD2") (pin "47") (pinfunction "VSS_47") (pintype "passive"))
      (node (ref "DD2") (pin "8") (pinfunction "VSSA_8") (pintype "passive"))
      (node (ref "GB1") (pin "2") (pinfunction "2_2") (pintype "passive"))
      (node (ref "L10") (pin "1") (pinfunction "1_1") (pintype "passive"))
      (node (ref "L19") (pin "1") (pinfunction "1_1") (pintype "passive"))
      (node (ref "L8") (pin "1") (pinfunction "1_1") (pintype "passive"))
      (node (ref "L9") (pin "1") (pinfunction "1_1") (pintype "passive"))
      (node (ref "R11") (pin "1") (pinfunction "1_1") (pintype "passive"))
      (node (ref "R2") (pin "1") (pinfunction "1_1") (pintype "passive"))
      (node (ref "R3") (pin "1") (pinfunction "1_1") (pintype "passive"))
      (node (ref "R5") (pin "1") (pinfunction "1_1") (pintype "passive"))
      (node (ref "R8") (pin "1") (pinfunction "1_1") (pintype "passive"))
      (node (ref "X1") (pin "2") (pinfunction "2_2") (pintype "passive"))
      (node (ref "X2") (pin "5") (pinfunction "5_5") (pintype "passive"))
      (node (ref "X3") (pin "2") (pinfunction "2_2") (pintype "passive"))
      (node (ref "X4") (pin "2") (pinfunction "2_2") (pintype "passive"))
      (node (ref "XT18") (pin "1") (pinfunction "1_1") (pintype "passive"))
      (node (ref "XT19") (pin "1") (pinfunction "1_1") (pintype "passive"))
      (node (ref "XT20") (pin "1") (pinfunction "1_1") (pintype "passive"))
      (node (ref "XT21") (pin "1") (pinfunction "1_1") (pintype "passive"))
      (node (ref "ZQ1") (pin "1") (pinfunction "GND_1") (pintype "passive"))
      (node (ref "ZQ1") (pin "2") (pinfunction "GND_2") (pintype "passive"))
    )
    (net (code "50") (name "Net-(C7-Pad2)") (class "Default")
      (node (ref "C7") (pin "2") (pinfunction "2_2") (pintype "passive"))
      (node (ref "L3") (pin "1") (pinfunction "1_1") (pintype "passive"))
    )
    (net (code "51") (name "Net-(C8-Pad2)") (class "Default")
      (node (ref "C8") (pin "2") (pinfunction "2_2") (pintype "passive"))
      (node (ref "L7") (pin "1") (pinfunction "1_1") (pintype "passive"))
    )
    (net (code "52") (name "Net-(C11-Pad2)") (class "Default")
      (node (ref "C11") (pin "2") (pinfunction "2_2") (pintype "passive"))
      (node (ref "C9") (pin "2") (pinfunction "2_2") (pintype "passive"))
      (node (ref "L4") (pin "2") (pinfunction "2_2") (pintype "passive"))
      (node (ref "L6") (pin "1") (pinfunction "1_1") (pintype "passive"))
    )
    (net (code "53") (name "Net-(C12-Pad1)") (class "Default")
      (node (ref "C12") (pin "1") (pinfunction "1_1") (pintype "passive"))
      (node (ref "L3") (pin "2") (pinfunction "2_2") (pintype "passive"))
      (node (ref "L4") (pin "1") (pinfunction "1_1") (pintype "passive"))
    )
    (net (code "54") (name "Net-(C13-Pad1)") (class "Default")
      (node (ref "C13") (pin "1") (pinfunction "1_1") (pintype "passive"))
      (node (ref "C9") (pin "1") (pinfunction "1_1") (pintype "passive"))
      (node (ref "L10") (pin "2") (pinfunction "2_2") (pintype "passive"))
      (node (ref "L7") (pin "2") (pinfunction "2_2") (pintype "passive"))
    )
    (net (code "55") (name "Net-(C14-Pad2)") (class "Default")
      (node (ref "C14") (pin "2") (pinfunction "2_2") (pintype "passive"))
      (node (ref "L13") (pin "1") (pinfunction "1_1") (pintype "passive"))
    )
    (net (code "56") (name "Net-(C15-Pad2)") (class "Default")
      (node (ref "C15") (pin "2") (pinfunction "2_2") (pintype "passive"))
      (node (ref "L16") (pin "1") (pinfunction "1_1") (pintype "passive"))
    )
    (net (code "57") (name "Net-(C16-Pad1)") (class "Default")
      (node (ref "C16") (pin "1") (pinfunction "1_1") (pintype "passive"))
      (node (ref "C19") (pin "1") (pinfunction "1_1") (pintype "passive"))
      (node (ref "L16") (pin "2") (pinfunction "2_2") (pintype "passive"))
      (node (ref "L19") (pin "2") (pinfunction "2_2") (pintype "passive"))
    )
    (net (code "58") (name "Net-(C16-Pad2)") (class "Default")
      (node (ref "C16") (pin "2") (pinfunction "2_2") (pintype "passive"))
      (node (ref "L14") (pin "2") (pinfunction "2_2") (pintype "passive"))
      (node (ref "X3") (pin "1") (pinfunction "1_1") (pintype "passive"))
    )
    (net (code "59") (name "Net-(C18-Pad1)") (class "Default")
      (node (ref "C18") (pin "1") (pinfunction "1_1") (pintype "passive"))
      (node (ref "L13") (pin "2") (pinfunction "2_2") (pintype "passive"))
      (node (ref "L14") (pin "1") (pinfunction "1_1") (pintype "passive"))
    )
    (net (code "60") (name "Net-(D1-ADC_REF)") (class "Default")
      (node (ref "C27") (pin "2") (pinfunction "2_2") (pintype "passive"))
      (node (ref "D1") (pin "5") (pinfunction "ADC_REF_5") (pintype "passive"))
    )
    (net (code "61") (name "Net-(D1-DLDO_1.1V)") (class "Default")
      (node (ref "C28") (pin "2") (pinfunction "2_2") (pintype "passive"))
      (node (ref "D1") (pin "13") (pinfunction "DLDO_1.1V_13") (pintype "passive"))
    )
    (net (code "62") (name "Net-(D1-RX_INN)") (class "Default")
      (node (ref "C8") (pin "1") (pinfunction "1_1") (pintype "passive"))
      (node (ref "D1") (pin "26") (pinfunction "RX_INN_26") (pintype "passive"))
      (node (ref "L9") (pin "2") (pinfunction "2_2") (pintype "passive"))
    )
    (net (code "63") (name "Net-(D1-RX_INP)") (class "Default")
      (node (ref "C7") (pin "1") (pinfunction "1_1") (pintype "passive"))
      (node (ref "D1") (pin "27") (pinfunction "RX_INP_27") (pintype "passive"))
      (node (ref "L8") (pin "2") (pinfunction "2_2") (pintype "passive"))
    )
    (net (code "64") (name "Net-(D1-TX_OUTN)") (class "Default")
      (node (ref "C15") (pin "1") (pinfunction "1_1") (pintype "passive"))
      (node (ref "D1") (pin "30") (pinfunction "TX_OUTN_30") (pintype "passive"))
      (node (ref "L11") (pin "1") (pinfunction "1_1") (pintype "passive"))
    )
    (net (code "65") (name "Net-(D1-TX_OUTP)") (class "Default")
      (node (ref "C14") (pin "1") (pinfunction "1_1") (pintype "passive"))
      (node (ref "D1") (pin "31") (pinfunction "TX_OUTP_31") (pintype "passive"))
      (node (ref "L12") (pin "1") (pinfunction "1_1") (pintype "passive"))
    )
    (net (code "66") (name "Net-(D1-XTAL_IN)") (class "Default")
      (node (ref "C23") (pin "1") (pinfunction "1_1") (pintype "passive"))
      (node (ref "D1") (pin "18") (pinfunction "XTAL_IN_18") (pintype "passive"))
      (node (ref "R4") (pin "1") (pinfunction "1_1") (pintype "passive"))
      (node (ref "R5") (pin "2") (pinfunction "2_2") (pintype "passive"))
    )
    (net (code "67") (name "Net-(DD1-~{RST})") (class "Default")
      (node (ref "DD1") (pin "9") (pinfunction "~{RST}_9") (pintype "passive"))
      (node (ref "R1") (pin "1") (pinfunction "1_1") (pintype "passive"))
    )
    (net (code "68") (name "Net-(DD1-~{SUSPEND})") (class "Default")
      (node (ref "DD1") (pin "11") (pinfunction "~{SUSPEND}_11") (pintype "passive"))
      (node (ref "R2") (pin "2") (pinfunction "2_2") (pintype "passive"))
    )
    (net (code "69") (name "Net-(DD2B-PC14-OSC32_IN)") (class "Default")
      (node (ref "C42") (pin "2") (pinfunction "2_2") (pintype "passive"))
      (node (ref "DD2") (pin "3") (pinfunction "PC14-OSC32_IN_3") (pintype "passive"))
      (node (ref "ZQ2") (pin "1") (pinfunction "1_1") (pintype "passive"))
    )
    (net (code "70") (name "Net-(DD2B-PC15-OSC32_OUT)") (class "Default")
      (node (ref "C43") (pin "2") (pinfunction "2_2") (pintype "passive"))
      (node (ref "DD2") (pin "4") (pinfunction "PC15-OSC32_OUT_4") (pintype "passive"))
      (node (ref "ZQ2") (pin "3") (pinfunction "3_3") (pintype "passive"))
    )
    (net (code "71") (name "Net-(GB1-Pad1)") (class "Default")
      (node (ref "GB1") (pin "1") (pinfunction "1_1") (pintype "passive"))
      (node (ref "SB9") (pin "2") (pinfunction "2_2") (pintype "passive"))
    )
    (net (code "72") (name "Net-(L5-Pad1)") (class "Default")
      (node (ref "L5") (pin "1") (pinfunction "1_1") (pintype "passive"))
      (node (ref "X2") (pin "1") (pinfunction "1_1") (pintype "passive"))
    )
    (net (code "73") (name "Net-(L6-Pad2)") (class "Default")
      (node (ref "L6") (pin "2") (pinfunction "2_2") (pintype "passive"))
      (node (ref "X1") (pin "1") (pinfunction "1_1") (pintype "passive"))
    )
    (net (code "74") (name "Net-(R10-Pad1)") (class "Default")
      (node (ref "R10") (pin "1") (pinfunction "1_1") (pintype "passive"))
      (node (ref "R11") (pin "2") (pinfunction "2_2") (pintype "passive"))
      (node (ref "VT2") (pin "1") (pinfunction "1_1") (pintype "passive"))
    )
    (net (code "75") (name "Net-(VT1-D)") (class "Default")
      (node (ref "R8") (pin "2") (pinfunction "2_2") (pintype "passive"))
      (node (ref "SB8") (pin "2") (pinfunction "2_2") (pintype "passive"))
      (node (ref "VT1") (pin "3") (pinfunction "D_3") (pintype "passive"))
    )
    (net (code "76") (name "Net-(VT1-G)") (class "Default")
      (node (ref "C39") (pin "1") (pinfunction "1_1") (pintype "passive"))
      (node (ref "R7") (pin "1") (pinfunction "1_1") (pintype "passive"))
      (node (ref "R9") (pin "2") (pinfunction "2_2") (pintype "passive"))
      (node (ref "VT1") (pin "1") (pinfunction "G_1") (pintype "passive"))
      (node (ref "VT2") (pin "3") (pinfunction "3_3") (pintype "passive"))
    )
    (net (code "77") (name "Net-(VT1-S)") (class "Default")
      (node (ref "C39") (pin "2") (pinfunction "2_2") (pintype "passive"))
      (node (ref "C40") (pin "2") (pinfunction "2_2") (pintype "passive"))
      (node (ref "R6") (pin "1") (pinfunction "1_1") (pintype "passive"))
      (node (ref "R7") (pin "2") (pinfunction "2_2") (pintype "passive"))
      (node (ref "VT1") (pin "2") (pinfunction "S_2") (pintype "passive"))
      (node (ref "VT2") (pin "2") (pinfunction "2_2") (pintype "passive"))
    )
    (net (code "78") (name "Net-(ZQ1-OUT)") (class "Default")
      (node (ref "C23") (pin "2") (pinfunction "2_2") (pintype "passive"))
      (node (ref "ZQ1") (pin "3") (pinfunction "OUT_3") (pintype "passive"))
    )
    (net (code "79") (name "unconnected-(D1-NC-Pad1)") (class "Default")
      (node (ref "D1") (pin "1") (pinfunction "NC_1") (pintype "passive+no_connect"))
    )
    (net (code "80") (name "unconnected-(D1-NC-Pad16)") (class "Default")
      (node (ref "D1") (pin "16") (pinfunction "NC_16") (pintype "passive+no_connect"))
    )
    (net (code "81") (name "unconnected-(D1-TMUX2-Pad24)") (class "Default")
      (node (ref "D1") (pin "24") (pinfunction "TMUX2_24") (pintype "passive+no_connect"))
    )
    (net (code "82") (name "unconnected-(D1-TMUX3-Pad23)") (class "Default")
      (node (ref "D1") (pin "23") (pinfunction "TMUX3_23") (pintype "passive+no_connect"))
    )
    (net (code "83") (name "unconnected-(DA3-N{slash}C-Pad4)") (class "Default")
      (node (ref "DA3") (pin "4") (pinfunction "N/C_4") (pintype "passive+no_connect"))
    )
    (net (code "84") (name "unconnected-(DD1-CST-Pad23)") (class "Default")
      (node (ref "DD1") (pin "23") (pinfunction "CST_23") (pintype "passive+no_connect"))
    )
    (net (code "85") (name "unconnected-(DD1-DCD-Pad1)") (class "Default")
      (node (ref "DD1") (pin "1") (pinfunction "DCD_1") (pintype "passive+no_connect"))
    )
    (net (code "86") (name "unconnected-(DD1-DSR-Pad27)") (class "Default")
      (node (ref "DD1") (pin "27") (pinfunction "DSR_27") (pintype "passive+no_connect"))
    )
    (net (code "87") (name "unconnected-(DD1-DTR-Pad28)") (class "Default")
      (node (ref "DD1") (pin "28") (pinfunction "DTR_28") (pintype "passive+no_connect"))
    )
    (net (code "88") (name "unconnected-(DD1-RI-Pad2)") (class "Default")
      (node (ref "DD1") (pin "2") (pinfunction "RI_2") (pintype "passive+no_connect"))
    )
    (net (code "89") (name "unconnected-(DD1-RTS-Pad24)") (class "Default")
      (node (ref "DD1") (pin "24") (pinfunction "RTS_24") (pintype "passive+no_connect"))
    )
    (net (code "90") (name "unconnected-(DD1-SUSPEND-Pad12)") (class "Default")
      (node (ref "DD1") (pin "12") (pinfunction "SUSPEND_12") (pintype "passive+no_connect"))
    )
    (net (code "91") (name "unconnected-(DD2A-PB15-Pad28)") (class "Default")
      (node (ref "DD2") (pin "28") (pinfunction "PB15_28") (pintype "passive+no_connect"))
    )
    (net (code "92") (name "unconnected-(X2-Pad4)") (class "Default")
      (node (ref "X2") (pin "4") (pinfunction "4_4") (pintype "passive+no_connect"))
    )
  )
)
